# DAC_Board.net
KiCad netlist of a schematic drawn in Altium Designer
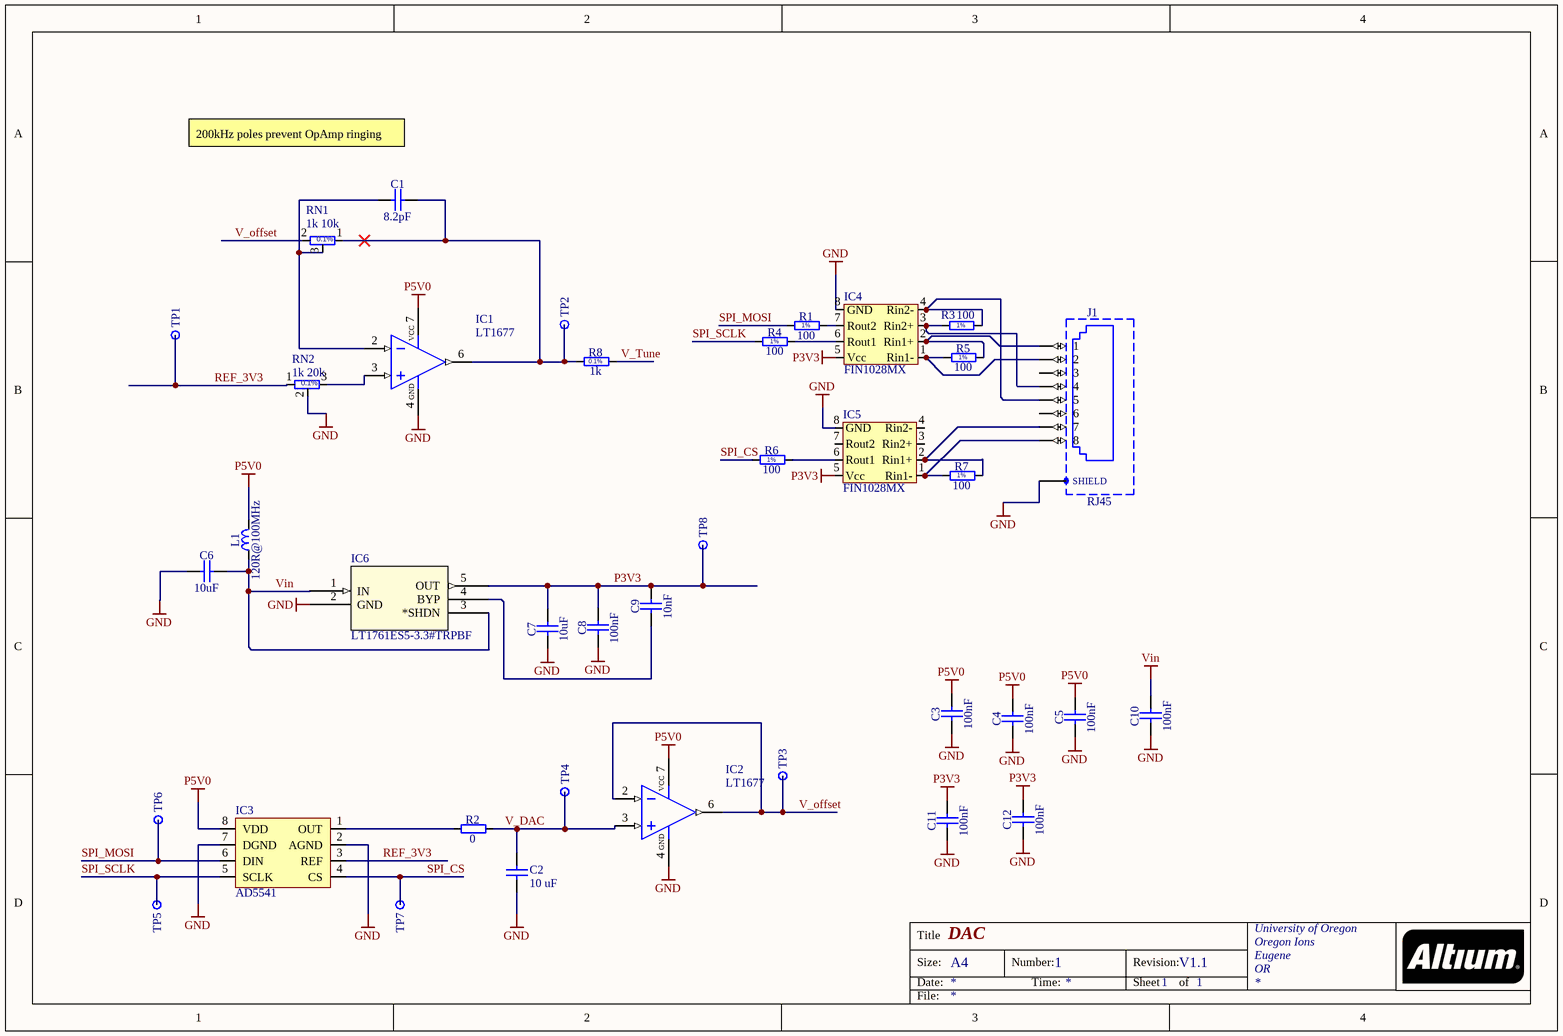
[diagram p0: DAC_Board.SchDoc]

(export (version "E")
  (design (tool "Eeschema 10.0.6"))
  (components
    (comp (ref "C1")
      (value "8.2pF")
      (footprint "CAPC1608X87N")
      (description "Non-polarised capacitor")
      (fields
        (field (name "PART NUMBER") "CC0603_8.2PF_50V_0.5PF_NP0")
        (field (name "VOLTAGE") "50V")
        (field (name "AUTHOR") "CERN DEM JLC")
      )
      (libsource (lib "Capacitors") (part "Capacitor - non polarized"))
    )
    (comp (ref "C2")
      (value "10 uF")
      (footprint "Capacitors SMD:CAPC5750X279N")
      (libsource (lib "Addons") (part "CAPF2220_10uF_25V_20%"))
    )
    (comp (ref "C3")
      (value "100nF")
      (footprint "CAPC1608X87N")
      (description "Non-polarised capacitor")
      (fields
        (field (name "PART NUMBER") "CC0603_100NF_50V_10%_X7R")
        (field (name "VOLTAGE") "50V")
        (field (name "AUTHOR") "CERN DEM JLC")
      )
      (libsource (lib "Capacitors") (part "Capacitor - non polarized"))
    )
    (comp (ref "C4")
      (value "100nF")
      (footprint "CAPC1608X87N")
      (description "Non-polarised capacitor")
      (fields
        (field (name "PART NUMBER") "CC0603_100NF_50V_10%_X7R")
        (field (name "VOLTAGE") "50V")
        (field (name "AUTHOR") "CERN DEM JLC")
      )
      (libsource (lib "Capacitors") (part "Capacitor - non polarized"))
    )
    (comp (ref "C5")
      (value "100nF")
      (footprint "CAPC1608X87N")
      (description "Non-polarised capacitor")
      (fields
        (field (name "PART NUMBER") "CC0603_100NF_50V_10%_X7R")
        (field (name "VOLTAGE") "50V")
        (field (name "AUTHOR") "CERN DEM JLC")
      )
      (libsource (lib "Capacitors") (part "Capacitor - non polarized"))
    )
    (comp (ref "C6")
      (value "10uF")
      (footprint "CAPC3216X180N")
      (description "Non-polarised capacitor")
      (fields
        (field (name "PART NUMBER") "CC1206_10UF_25V_10%_X7R")
        (field (name "VOLTAGE") "25V")
        (field (name "AUTHOR") "CERN DEM JLC")
      )
      (libsource (lib "Capacitors") (part "Capacitor - non polarized"))
    )
    (comp (ref "C7")
      (value "10uF")
      (footprint "CAPC3216X180N")
      (description "Non-polarised capacitor")
      (fields
        (field (name "PART NUMBER") "CC1206_10UF_25V_10%_X7R")
        (field (name "VOLTAGE") "25V")
        (field (name "AUTHOR") "CERN DEM JLC")
      )
      (libsource (lib "Capacitors") (part "Capacitor - non polarized"))
    )
    (comp (ref "C8")
      (value "100nF")
      (footprint "CAPC1608X87N")
      (description "Non-polarised capacitor")
      (fields
        (field (name "PART NUMBER") "CC0603_100NF_50V_10%_X7R")
        (field (name "VOLTAGE") "50V")
        (field (name "AUTHOR") "CERN DEM JLC")
      )
      (libsource (lib "Capacitors") (part "Capacitor - non polarized"))
    )
    (comp (ref "C9")
      (value "10nF")
      (footprint "CAPC1608X87N")
      (description "Non-polarised capacitor")
      (fields
        (field (name "PART NUMBER") "CC0603_10NF_50V_10%_X7R")
        (field (name "VOLTAGE") "50V")
        (field (name "AUTHOR") "CERN DEM JLC")
      )
      (libsource (lib "Capacitors") (part "Capacitor - non polarized"))
    )
    (comp (ref "C10")
      (value "100nF")
      (footprint "CAPC1608X87N")
      (description "Non-polarised capacitor")
      (fields
        (field (name "PART NUMBER") "CC0603_100NF_50V_10%_X7R")
        (field (name "VOLTAGE") "50V")
        (field (name "AUTHOR") "CERN DEM JLC")
      )
      (libsource (lib "Capacitors") (part "Capacitor - non polarized"))
    )
    (comp (ref "C11")
      (value "100nF")
      (footprint "CAPC1608X87N")
      (description "Non-polarised capacitor")
      (fields
        (field (name "PART NUMBER") "CC0603_100NF_50V_10%_X7R")
        (field (name "VOLTAGE") "50V")
        (field (name "AUTHOR") "CERN DEM JLC")
      )
      (libsource (lib "Capacitors") (part "Capacitor - non polarized"))
    )
    (comp (ref "C12")
      (value "100nF")
      (footprint "CAPC1608X87N")
      (description "Non-polarised capacitor")
      (fields
        (field (name "PART NUMBER") "CC0603_100NF_50V_10%_X7R")
        (field (name "VOLTAGE") "50V")
        (field (name "AUTHOR") "CERN DEM JLC")
      )
      (libsource (lib "Capacitors") (part "Capacitor - non polarized"))
    )
    (comp (ref "IC1")
      (value "LT1677")
      (footprint "SOIC127P600X175-8N")
      (description "0-5 V Rail to Rail op amp")
      (libsource (lib "LIBRARY_SCH") (part "LT1677"))
    )
    (comp (ref "IC2")
      (value "LT1677")
      (footprint "SOIC127P600X175-8N")
      (description "0-5 V Rail to Rail op amp")
      (libsource (lib "LIBRARY_SCH") (part "LT1677"))
    )
    (comp (ref "IC3")
      (value "AD5541")
      (footprint "AD5541")
      (description "16 bit serial DAC")
      (libsource (lib "LIBRARY_SCH") (part "AD5541"))
    )
    (comp (ref "IC4")
      (value "FIN1028MX")
      (footprint "FIN1028MX")
      (description "LVDS to TTL")
      (libsource (lib "LIBRARY_SCH") (part "FIN1028MX"))
    )
    (comp (ref "IC5")
      (value "FIN1028MX")
      (footprint "FIN1028MX")
      (description "LVDS to TTL")
      (libsource (lib "LIBRARY_SCH") (part "FIN1028MX"))
    )
    (comp (ref "IC6")
      (value "LT1761ES5-3.3#TRPBF")
      (footprint "LDO")
      (description "3.3 V LDO")
      (libsource (lib "LIBRARY_SCH") (part "LT1761ES5-3.3#TRPBF"))
    )
    (comp (ref "J1")
      (value "RJ45")
      (footprint "TYCO_6368150-1")
      (description "Connector RJ45 + Shield")
      (fields
        (field (name "PART NUMBER") "TYCO_6368150-1")
        (field (name "MANUFACTURER") "TYCO ELECTRONICS")
        (field (name "AUTHOR") "CERN DEM MR")
      )
      (libsource (lib "Connectors") (part "Connector RJ45 + Shield"))
    )
    (comp (ref "L1")
      (value "120R@100MHz")
      (footprint "INDC1608X95N")
      (description "Inductor")
      (fields
        (field (name "PART NUMBER") "IND0603_MURATA_BLM18PG121SN1D")
        (field (name "POWER") "2A")
        (field (name "AUTHOR") "CERN DEM BC")
      )
      (libsource (lib "Inductors & Transformers") (part "Inductor"))
    )
    (comp (ref "R1")
      (value "100")
      (footprint "RESC1608X55N")
      (description "Resistor - 1%")
      (fields
        (field (name "PART NUMBER") "R0603_100R_1%_0.1W_100PPM")
        (field (name "POWER") "0.1W")
        (field (name "AUTHOR") "CERN DEM JLC")
      )
      (libsource (lib "Resistors") (part "Resistor - 1%"))
    )
    (comp (ref "R2")
      (value "0")
      (footprint "RESC1608X55N")
      (description "Resistor")
      (fields
        (field (name "PART NUMBER") "R0603_0R_JUMPER")
        (field (name "MANUFACTURER") "GENERIC")
        (field (name "AUTHOR") "CERN DEM JLC")
      )
      (libsource (lib "Resistors") (part "Resistor"))
    )
    (comp (ref "R3")
      (value "100")
      (footprint "RESC1608X55N")
      (description "Resistor - 1%")
      (fields
        (field (name "PART NUMBER") "R0603_100R_1%_0.1W_100PPM")
        (field (name "POWER") "0.1W")
        (field (name "AUTHOR") "CERN DEM JLC")
      )
      (libsource (lib "Resistors") (part "Resistor - 1%"))
    )
    (comp (ref "R4")
      (value "100")
      (footprint "RESC1608X55N")
      (description "Resistor - 1%")
      (fields
        (field (name "PART NUMBER") "R0603_100R_1%_0.1W_100PPM")
        (field (name "POWER") "0.1W")
        (field (name "AUTHOR") "CERN DEM JLC")
      )
      (libsource (lib "Resistors") (part "Resistor - 1%"))
    )
    (comp (ref "R5")
      (value "100")
      (footprint "RESC1608X55N")
      (description "Resistor - 1%")
      (fields
        (field (name "PART NUMBER") "R0603_100R_1%_0.1W_100PPM")
        (field (name "POWER") "0.1W")
        (field (name "AUTHOR") "CERN DEM JLC")
      )
      (libsource (lib "Resistors") (part "Resistor - 1%"))
    )
    (comp (ref "R6")
      (value "100")
      (footprint "RESC1608X55N")
      (description "Resistor - 1%")
      (fields
        (field (name "PART NUMBER") "R0603_100R_1%_0.1W_100PPM")
        (field (name "POWER") "0.1W")
        (field (name "AUTHOR") "CERN DEM JLC")
      )
      (libsource (lib "Resistors") (part "Resistor - 1%"))
    )
    (comp (ref "R7")
      (value "100")
      (footprint "RESC1608X55N")
      (description "Resistor - 1%")
      (fields
        (field (name "PART NUMBER") "R0603_100R_1%_0.1W_100PPM")
        (field (name "POWER") "0.1W")
        (field (name "AUTHOR") "CERN DEM JLC")
      )
      (libsource (lib "Resistors") (part "Resistor - 1%"))
    )
    (comp (ref "R8")
      (value "1k")
      (footprint "RESC1608X55N")
      (description "Resistor - 0.1%")
      (fields
        (field (name "PART NUMBER") "R0603_1K0_0.1%_0.063W_10PPM")
        (field (name "POWER") "0.063W")
        (field (name "AUTHOR") "CERN DEM JLC")
      )
      (libsource (lib "Resistors") (part "Resistor - 0.1%"))
    )
    (comp (ref "RN1")
      (value "~")
      (footprint "SOT95P230X112-3N")
      (description "Resistor Network Divider - 0.1%")
      (libsource (lib "LIBRARY_SCH") (part "RN_1k_10k_VISHAY_MPMT10011002AT1"))
    )
    (comp (ref "RN2")
      (value "~")
      (footprint "SOT95P230X112-3N")
      (description "Resistor Network Divider - 0.1%")
      (libsource (lib "LIBRARY_SCH") (part "RN_1k_20k_VISHAY_MPMT10012002AT1"))
    )
    (comp (ref "TP1")
      (value "Test Point")
      (footprint "TPS127")
      (fields (field (name "PART NUMBER") "SMD_PAD_1.27X1.27MM") (field (name "AUTHOR") "CERN DEM JLC"))
      (libsource (lib "Eletro-mechanical") (part "Test Point"))
    )
    (comp (ref "TP2")
      (value "Test Point")
      (footprint "TPS127")
      (fields (field (name "PART NUMBER") "SMD_PAD_1.27X1.27MM") (field (name "AUTHOR") "CERN DEM JLC"))
      (libsource (lib "Eletro-mechanical") (part "Test Point"))
    )
    (comp (ref "TP3")
      (value "Test Point")
      (footprint "TPS127")
      (fields (field (name "PART NUMBER") "SMD_PAD_1.27X1.27MM") (field (name "AUTHOR") "CERN DEM JLC"))
      (libsource (lib "Eletro-mechanical") (part "Test Point"))
    )
    (comp (ref "TP4")
      (value "Test Point")
      (footprint "TPS127")
      (fields (field (name "PART NUMBER") "SMD_PAD_1.27X1.27MM") (field (name "AUTHOR") "CERN DEM JLC"))
      (libsource (lib "Eletro-mechanical") (part "Test Point"))
    )
    (comp (ref "TP5")
      (value "Test Point")
      (footprint "TPS127")
      (fields (field (name "PART NUMBER") "SMD_PAD_1.27X1.27MM") (field (name "AUTHOR") "CERN DEM JLC"))
      (libsource (lib "Eletro-mechanical") (part "Test Point"))
    )
    (comp (ref "TP6")
      (value "Test Point")
      (footprint "TPS127")
      (fields (field (name "PART NUMBER") "SMD_PAD_1.27X1.27MM") (field (name "AUTHOR") "CERN DEM JLC"))
      (libsource (lib "Eletro-mechanical") (part "Test Point"))
    )
    (comp (ref "TP7")
      (value "Test Point")
      (footprint "TPS127")
      (fields (field (name "PART NUMBER") "SMD_PAD_1.27X1.27MM") (field (name "AUTHOR") "CERN DEM JLC"))
      (libsource (lib "Eletro-mechanical") (part "Test Point"))
    )
    (comp (ref "TP8")
      (value "Test Point")
      (footprint "TPS127")
      (fields (field (name "PART NUMBER") "SMD_PAD_1.27X1.27MM") (field (name "AUTHOR") "CERN DEM JLC"))
      (libsource (lib "Eletro-mechanical") (part "Test Point"))
    )
  )
  (nets
    (net (code "1") (name "/REF_3V3") (class "Default")
      (node (ref "IC3") (pin "3") (pinfunction "REF_3") (pintype "passive"))
      (node (ref "RN2") (pin "1") (pinfunction "1_1") (pintype "passive"))
      (node (ref "TP1") (pin "1") (pinfunction "1_1") (pintype "bidirectional"))
    )
    (net (code "2") (name "/SPI_CS") (class "Default")
      (node (ref "IC3") (pin "4") (pinfunction "CS_4") (pintype "passive"))
      (node (ref "R6") (pin "1") (pinfunction "1_1") (pintype "passive"))
      (node (ref "TP7") (pin "1") (pinfunction "1_1") (pintype "bidirectional"))
    )
    (net (code "3") (name "/SPI_MOSI") (class "Default")
      (node (ref "IC3") (pin "6") (pinfunction "DIN_6") (pintype "passive"))
      (node (ref "R1") (pin "1") (pinfunction "1_1") (pintype "passive"))
      (node (ref "TP6") (pin "1") (pinfunction "1_1") (pintype "bidirectional"))
    )
    (net (code "4") (name "/SPI_SCLK") (class "Default")
      (node (ref "IC3") (pin "5") (pinfunction "SCLK_5") (pintype "passive"))
      (node (ref "R4") (pin "1") (pinfunction "1_1") (pintype "passive"))
      (node (ref "TP5") (pin "1") (pinfunction "1_1") (pintype "bidirectional"))
    )
    (net (code "5") (name "/V_DAC") (class "Default")
      (node (ref "C2") (pin "2") (pinfunction "2_2") (pintype "passive"))
      (node (ref "IC2") (pin "3") (pinfunction "IN+_3") (pintype "input"))
      (node (ref "R2") (pin "2") (pinfunction "2_2") (pintype "passive"))
      (node (ref "TP4") (pin "1") (pinfunction "1_1") (pintype "bidirectional"))
    )
    (net (code "6") (name "/V_Tune") (class "Default")
      (node (ref "R8") (pin "2") (pinfunction "2_2") (pintype "passive"))
    )
    (net (code "7") (name "/V_offset") (class "Default")
      (node (ref "IC2") (pin "2") (pinfunction "IN-_2") (pintype "input"))
      (node (ref "IC2") (pin "6") (pinfunction "OUT_6") (pintype "output"))
      (node (ref "RN1") (pin "2") (pinfunction "2_2") (pintype "passive"))
      (node (ref "TP3") (pin "1") (pinfunction "1_1") (pintype "bidirectional"))
    )
    (net (code "8") (name "GND") (class "Default")
      (node (ref "C10") (pin "1") (pinfunction "1_1") (pintype "passive"))
      (node (ref "C11") (pin "1") (pinfunction "1_1") (pintype "passive"))
      (node (ref "C12") (pin "1") (pinfunction "1_1") (pintype "passive"))
      (node (ref "C2") (pin "1") (pinfunction "1_1") (pintype "passive"))
      (node (ref "C3") (pin "1") (pinfunction "1_1") (pintype "passive"))
      (node (ref "C4") (pin "1") (pinfunction "1_1") (pintype "passive"))
      (node (ref "C5") (pin "1") (pinfunction "1_1") (pintype "passive"))
      (node (ref "C6") (pin "1") (pinfunction "1_1") (pintype "passive"))
      (node (ref "C7") (pin "1") (pinfunction "1_1") (pintype "passive"))
      (node (ref "C8") (pin "1") (pinfunction "1_1") (pintype "passive"))
      (node (ref "IC1") (pin "4") (pinfunction "GND_4") (pintype "power_in"))
      (node (ref "IC2") (pin "4") (pinfunction "GND_4") (pintype "power_in"))
      (node (ref "IC3") (pin "2") (pinfunction "AGND_2") (pintype "passive"))
      (node (ref "IC3") (pin "7") (pinfunction "DGND_7") (pintype "passive"))
      (node (ref "IC4") (pin "8") (pinfunction "GND_8") (pintype "passive"))
      (node (ref "IC5") (pin "8") (pinfunction "GND_8") (pintype "passive"))
      (node (ref "IC6") (pin "2") (pinfunction "GND_2") (pintype "power_in"))
      (node (ref "J1") (pin "SHIELD") (pinfunction "SHIELD_SHIELD") (pintype "passive"))
      (node (ref "RN2") (pin "2") (pinfunction "2_2") (pintype "passive"))
    )
    (net (code "9") (name "Net-(IC1-IN+)") (class "Default")
      (node (ref "IC1") (pin "3") (pinfunction "IN+_3") (pintype "input"))
      (node (ref "RN2") (pin "3") (pinfunction "3_3") (pintype "passive"))
    )
    (net (code "10") (name "Net-(IC1-IN-)") (class "Default")
      (node (ref "C1") (pin "1") (pinfunction "1_1") (pintype "passive"))
      (node (ref "IC1") (pin "2") (pinfunction "IN-_2") (pintype "input"))
      (node (ref "RN1") (pin "3") (pinfunction "3_3") (pintype "passive"))
    )
    (net (code "11") (name "Net-(IC1-OUT)") (class "Default")
      (node (ref "C1") (pin "2") (pinfunction "2_2") (pintype "passive"))
      (node (ref "IC1") (pin "6") (pinfunction "OUT_6") (pintype "output"))
      (node (ref "R8") (pin "1") (pinfunction "1_1") (pintype "passive"))
      (node (ref "RN1") (pin "1") (pinfunction "1_1") (pintype "passive"))
      (node (ref "TP2") (pin "1") (pinfunction "1_1") (pintype "bidirectional"))
    )
    (net (code "12") (name "Net-(IC3-OUT)") (class "Default")
      (node (ref "IC3") (pin "1") (pinfunction "OUT_1") (pintype "passive"))
      (node (ref "R2") (pin "1") (pinfunction "1_1") (pintype "passive"))
    )
    (net (code "13") (name "Net-(IC4-Rin1+)") (class "Default")
      (node (ref "IC4") (pin "2") (pinfunction "Rin1+_2") (pintype "passive"))
      (node (ref "J1") (pin "1") (pinfunction "1_1") (pintype "bidirectional"))
      (node (ref "R5") (pin "2") (pinfunction "2_2") (pintype "passive"))
    )
    (net (code "14") (name "Net-(IC4-Rin1-)") (class "Default")
      (node (ref "IC4") (pin "1") (pinfunction "Rin1-_1") (pintype "passive"))
      (node (ref "J1") (pin "2") (pinfunction "2_2") (pintype "bidirectional"))
      (node (ref "R5") (pin "1") (pinfunction "1_1") (pintype "passive"))
    )
    (net (code "15") (name "Net-(IC4-Rin2+)") (class "Default")
      (node (ref "IC4") (pin "3") (pinfunction "Rin2+_3") (pintype "passive"))
      (node (ref "J1") (pin "4") (pinfunction "4_4") (pintype "bidirectional"))
      (node (ref "R3") (pin "1") (pinfunction "1_1") (pintype "passive"))
    )
    (net (code "16") (name "Net-(IC4-Rin2-)") (class "Default")
      (node (ref "IC4") (pin "4") (pinfunction "Rin2-_4") (pintype "passive"))
      (node (ref "J1") (pin "5") (pinfunction "5_5") (pintype "bidirectional"))
      (node (ref "R3") (pin "2") (pinfunction "2_2") (pintype "passive"))
    )
    (net (code "17") (name "Net-(IC4-Rout1)") (class "Default")
      (node (ref "IC4") (pin "6") (pinfunction "Rout1_6") (pintype "passive"))
      (node (ref "R4") (pin "2") (pinfunction "2_2") (pintype "passive"))
    )
    (net (code "18") (name "Net-(IC4-Rout2)") (class "Default")
      (node (ref "IC4") (pin "7") (pinfunction "Rout2_7") (pintype "passive"))
      (node (ref "R1") (pin "2") (pinfunction "2_2") (pintype "passive"))
    )
    (net (code "19") (name "Net-(IC5-Rin1+)") (class "Default")
      (node (ref "IC5") (pin "2") (pinfunction "Rin1+_2") (pintype "passive"))
      (node (ref "J1") (pin "7") (pinfunction "7_7") (pintype "bidirectional"))
      (node (ref "R7") (pin "2") (pinfunction "2_2") (pintype "passive"))
    )
    (net (code "20") (name "Net-(IC5-Rin1-)") (class "Default")
      (node (ref "IC5") (pin "1") (pinfunction "Rin1-_1") (pintype "passive"))
      (node (ref "J1") (pin "8") (pinfunction "8_8") (pintype "bidirectional"))
      (node (ref "R7") (pin "1") (pinfunction "1_1") (pintype "passive"))
    )
    (net (code "21") (name "Net-(IC5-Rout1)") (class "Default")
      (node (ref "IC5") (pin "6") (pinfunction "Rout1_6") (pintype "passive"))
      (node (ref "R6") (pin "2") (pinfunction "2_2") (pintype "passive"))
    )
    (net (code "22") (name "Net-(IC6-BYP)") (class "Default")
      (node (ref "C9") (pin "1") (pinfunction "1_1") (pintype "passive"))
      (node (ref "IC6") (pin "4") (pinfunction "BYP_4") (pintype "passive"))
    )
    (net (code "23") (name "P3V3") (class "Default")
      (node (ref "C11") (pin "2") (pinfunction "2_2") (pintype "passive"))
      (node (ref "C12") (pin "2") (pinfunction "2_2") (pintype "passive"))
      (node (ref "C7") (pin "2") (pinfunction "2_2") (pintype "passive"))
      (node (ref "C8") (pin "2") (pinfunction "2_2") (pintype "passive"))
      (node (ref "C9") (pin "2") (pinfunction "2_2") (pintype "passive"))
      (node (ref "IC4") (pin "5") (pinfunction "Vcc_5") (pintype "passive"))
      (node (ref "IC5") (pin "5") (pinfunction "Vcc_5") (pintype "passive"))
      (node (ref "IC6") (pin "5") (pinfunction "OUT_5") (pintype "output"))
      (node (ref "TP8") (pin "1") (pinfunction "1_1") (pintype "bidirectional"))
    )
    (net (code "24") (name "P5V0") (class "Default")
      (node (ref "C3") (pin "2") (pinfunction "2_2") (pintype "passive"))
      (node (ref "C4") (pin "2") (pinfunction "2_2") (pintype "passive"))
      (node (ref "C5") (pin "2") (pinfunction "2_2") (pintype "passive"))
      (node (ref "IC1") (pin "7") (pinfunction "Vs+_7") (pintype "power_in"))
      (node (ref "IC2") (pin "7") (pinfunction "Vs+_7") (pintype "power_in"))
      (node (ref "IC3") (pin "8") (pinfunction "VDD_8") (pintype "passive"))
      (node (ref "L1") (pin "2") (pinfunction "2_2") (pintype "passive"))
    )
    (net (code "25") (name "Vin") (class "Default")
      (node (ref "C10") (pin "2") (pinfunction "2_2") (pintype "passive"))
      (node (ref "C6") (pin "2") (pinfunction "2_2") (pintype "passive"))
      (node (ref "IC6") (pin "1") (pinfunction "IN_1") (pintype "input"))
      (node (ref "IC6") (pin "3") (pinfunction "*SHDN_3") (pintype "passive"))
      (node (ref "L1") (pin "1") (pinfunction "1_1") (pintype "passive"))
    )
    (net (code "26") (name "unconnected-(IC5-Rin2+-Pad3)") (class "Default")
      (node (ref "IC5") (pin "3") (pinfunction "Rin2+_3") (pintype "passive"))
    )
    (net (code "27") (name "unconnected-(IC5-Rin2--Pad4)") (class "Default")
      (node (ref "IC5") (pin "4") (pinfunction "Rin2-_4") (pintype "passive"))
    )
    (net (code "28") (name "unconnected-(IC5-Rout2-Pad7)") (class "Default")
      (node (ref "IC5") (pin "7") (pinfunction "Rout2_7") (pintype "passive"))
    )
    (net (code "29") (name "unconnected-(J1-Pad3)") (class "Default")
      (node (ref "J1") (pin "3") (pinfunction "3_3") (pintype "bidirectional"))
    )
    (net (code "30") (name "unconnected-(J1-Pad6)") (class "Default")
      (node (ref "J1") (pin "6") (pinfunction "6_6") (pintype "bidirectional"))
    )
  )
)
